# NNLightSwitcher_eMMC_SD.net
KiCad netlist of a schematic drawn in Altium Designer
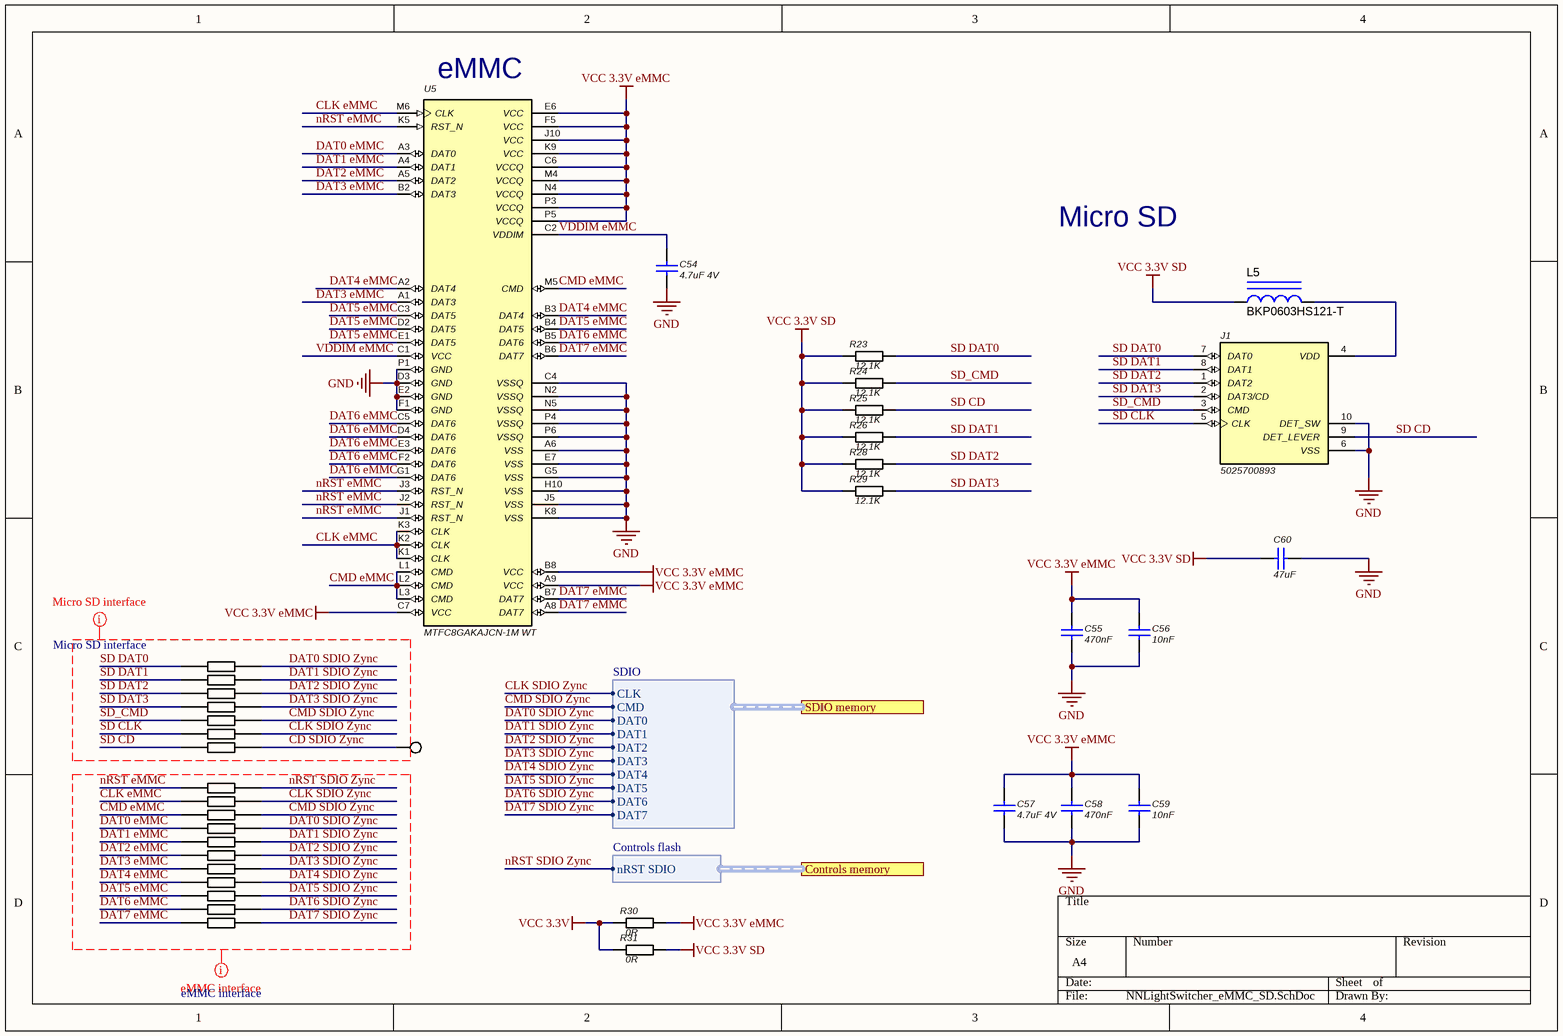
[diagram p0: NNLightSwitcher_eMMC_SD.SchDoc]

(export (version "E")
  (design (tool "Eeschema 10.0.6"))
  (components
    (comp (ref "C54")
      (value "4.7uF 4V")
      (footprint "0402")
      (libsource (lib "NNLightSwitcher") (part "Capacitor 4.7uF 4V"))
    )
    (comp (ref "C55")
      (value "470nF")
      (footprint "0402")
      (libsource (lib "NNLightSwitcher") (part "Capacitor 470nF"))
    )
    (comp (ref "C56")
      (value "10nF")
      (footprint "0402")
      (libsource (lib "NNLightSwitcher") (part "Capacitor 10nF"))
    )
    (comp (ref "C57")
      (value "4.7uF 4V")
      (footprint "0402")
      (libsource (lib "NNLightSwitcher") (part "Capacitor 4.7uF 4V"))
    )
    (comp (ref "C58")
      (value "470nF")
      (footprint "0402")
      (libsource (lib "NNLightSwitcher") (part "Capacitor 470nF"))
    )
    (comp (ref "C59")
      (value "10nF")
      (footprint "0402")
      (libsource (lib "NNLightSwitcher") (part "Capacitor 10nF"))
    )
    (comp (ref "C60")
      (value "47uF")
      (footprint "Res_0805")
      (libsource (lib "NNLightSwitcher") (part "Capacitor 47uF"))
    )
    (comp (ref "J1")
      (value "5025700893")
      (footprint "MOLEX_5025700893")
      (description "1.10mm Pitch microSD Memory Card Connector%2C Normal Mount Surface Mount%2C Push-Push Type")
      (libsource (lib "NNLightSwitcher") (part "Micro SD connector"))
    )
    (comp (ref "L5")
      (value "BKP0603HS121-T")
      (footprint "*0603")
      (description "Inductor, Multilayer, Ferrite bad")
      (fields (field (name "PARTNUMBER") "LQG15HS3N9S02D") (field (name "MANUFACTURER") "MuRata"))
      (libsource (lib "NNLightSwitcher") (part "BKP0603HS121-T"))
    )
    (comp (ref "R23")
      (value "12.1K")
      (footprint "0402")
      (libsource (lib "NNLightSwitcher") (part "Resistor 12.1K"))
    )
    (comp (ref "R24")
      (value "12.1K")
      (footprint "0402")
      (libsource (lib "NNLightSwitcher") (part "Resistor 12.1K"))
    )
    (comp (ref "R25")
      (value "12.1K")
      (footprint "0402")
      (libsource (lib "NNLightSwitcher") (part "Resistor 12.1K"))
    )
    (comp (ref "R26")
      (value "12.1K")
      (footprint "0402")
      (libsource (lib "NNLightSwitcher") (part "Resistor 12.1K"))
    )
    (comp (ref "R28")
      (value "12.1K")
      (footprint "0402")
      (libsource (lib "NNLightSwitcher") (part "Resistor 12.1K"))
    )
    (comp (ref "R29")
      (value "12.1K")
      (footprint "0402")
      (libsource (lib "NNLightSwitcher") (part "Resistor 12.1K"))
    )
    (comp (ref "R30")
      (value "0R")
      (footprint "0402")
      (libsource (lib "NNLightSwitcher") (part "Resistor 0R"))
    )
    (comp (ref "R31")
      (value "0R")
      (footprint "0402")
      (libsource (lib "NNLightSwitcher") (part "Resistor 0R"))
    )
    (comp (ref "RN25")
      (value "EXB-2HV431JV")
      (footprint "*RESCAXE50P380X160X55-16N")
      (description "Res Thick Film Array")
      (libsource (lib "NNLightSwitcher") (part "EXB-2HV431JV"))
    )
    (comp (ref "RN26")
      (value "EXB-2HV431JV")
      (footprint "*RESCAXE50P380X160X55-16N")
      (description "Res Thick Film Array")
      (libsource (lib "NNLightSwitcher") (part "EXB-2HV431JV"))
    )
    (comp (ref "RN27")
      (value "EXB-2HV431JV")
      (footprint "*RESCAXE50P380X160X55-16N")
      (description "Res Thick Film Array")
      (libsource (lib "NNLightSwitcher") (part "EXB-2HV431JV"))
    )
    (comp (ref "TP66")
      (value "Test point")
      (footprint "Testpoint_with_pad")
      (description "Test Point, Miniature, SMT")
      (libsource (lib "NNLightSwitcher") (part "Test point"))
    )
    (comp (ref "U5")
      (value "MTFC8GAKAJCN-1M WT")
      (footprint "*BGA153N50P14X14_1150X1300X100_MTFC4GACAAAM-1M_WT(Primary)")
      (description "J54A eMMC 32G ECCN: 3A991 / HTS: 8542.32.0070")
      (libsource (lib "NNLightSwitcher") (part "MTFC4GACAAAM-1M_WT"))
    )
  )
  (nets
    (net (code "4") (name "/CD SDIO Zync") (class "Default")
      (node (ref "RN25") (pin "15") (pinfunction "2_15") (pintype "passive"))
      (node (ref "TP66") (pin "1") (pintype "passive"))
    )
    (net (code "5") (name "/CLK SDIO Zync") (class "Default")
      (node (ref "RN25") (pin "11") (pinfunction "2_11") (pintype "passive"))
      (node (ref "RN26") (pin "14") (pinfunction "2_14") (pintype "passive"))
    )
    (net (code "6") (name "/CLK eMMC") (class "Default")
      (node (ref "RN26") (pin "3") (pinfunction "1_3") (pintype "passive"))
      (node (ref "U5") (pin "K1") (pinfunction "CLK_K1") (pintype "bidirectional"))
      (node (ref "U5") (pin "K2") (pinfunction "CLK_K2") (pintype "bidirectional"))
      (node (ref "U5") (pin "K3") (pinfunction "CLK_K3") (pintype "bidirectional"))
      (node (ref "U5") (pin "M6") (pinfunction "CLK_M6") (pintype "input"))
    )
    (net (code "7") (name "/CMD SDIO Zync") (class "Default")
      (node (ref "RN25") (pin "14") (pinfunction "2_14") (pintype "passive"))
      (node (ref "RN26") (pin "11") (pinfunction "2_11") (pintype "passive"))
    )
    (net (code "8") (name "/CMD eMMC") (class "Default")
      (node (ref "RN26") (pin "6") (pinfunction "1_6") (pintype "passive"))
      (node (ref "U5") (pin "L1") (pinfunction "CMD_L1") (pintype "bidirectional"))
      (node (ref "U5") (pin "L2") (pinfunction "CMD_L2") (pintype "bidirectional"))
      (node (ref "U5") (pin "L3") (pinfunction "CMD_L3") (pintype "bidirectional"))
      (node (ref "U5") (pin "M5") (pinfunction "CMD_M5") (pintype "bidirectional"))
    )
    (net (code "9") (name "/DAT0 SDIO Zync") (class "Default")
      (node (ref "RN25") (pin "9") (pinfunction "2_9") (pintype "passive"))
      (node (ref "RN26") (pin "16") (pinfunction "2_16") (pintype "passive"))
    )
    (net (code "10") (name "/DAT0 eMMC") (class "Default")
      (node (ref "RN26") (pin "1") (pinfunction "1_1") (pintype "passive"))
      (node (ref "U5") (pin "A3") (pinfunction "DAT0_A3") (pintype "bidirectional"))
    )
    (net (code "11") (name "/DAT1 SDIO Zync") (class "Default")
      (node (ref "RN25") (pin "10") (pinfunction "2_10") (pintype "passive"))
      (node (ref "RN26") (pin "15") (pinfunction "2_15") (pintype "passive"))
    )
    (net (code "12") (name "/DAT1 eMMC") (class "Default")
      (node (ref "RN26") (pin "2") (pinfunction "1_2") (pintype "passive"))
      (node (ref "U5") (pin "A4") (pinfunction "DAT1_A4") (pintype "bidirectional"))
    )
    (net (code "13") (name "/DAT2 SDIO Zync") (class "Default")
      (node (ref "RN25") (pin "12") (pinfunction "2_12") (pintype "passive"))
      (node (ref "RN26") (pin "13") (pinfunction "2_13") (pintype "passive"))
    )
    (net (code "14") (name "/DAT2 eMMC") (class "Default")
      (node (ref "RN26") (pin "4") (pinfunction "1_4") (pintype "passive"))
      (node (ref "U5") (pin "A5") (pinfunction "DAT2_A5") (pintype "bidirectional"))
    )
    (net (code "15") (name "/DAT3 SDIO Zync") (class "Default")
      (node (ref "RN25") (pin "13") (pinfunction "2_13") (pintype "passive"))
      (node (ref "RN26") (pin "12") (pinfunction "2_12") (pintype "passive"))
    )
    (net (code "16") (name "/DAT3 eMMC") (class "Default")
      (node (ref "RN26") (pin "5") (pinfunction "1_5") (pintype "passive"))
      (node (ref "U5") (pin "A1") (pinfunction "DAT3_A1") (pintype "bidirectional"))
      (node (ref "U5") (pin "B2") (pinfunction "DAT3_B2") (pintype "bidirectional"))
    )
    (net (code "17") (name "/DAT4 SDIO Zync") (class "Default")
      (node (ref "RN26") (pin "10") (pinfunction "2_10") (pintype "passive"))
    )
    (net (code "18") (name "/DAT4 eMMC") (class "Default")
      (node (ref "RN26") (pin "7") (pinfunction "1_7") (pintype "passive"))
      (node (ref "U5") (pin "A2") (pinfunction "DAT4_A2") (pintype "bidirectional"))
      (node (ref "U5") (pin "B3") (pinfunction "DAT4_B3") (pintype "bidirectional"))
    )
    (net (code "19") (name "/DAT5 SDIO Zync") (class "Default")
      (node (ref "RN26") (pin "9") (pinfunction "2_9") (pintype "passive"))
    )
    (net (code "20") (name "/DAT5 eMMC") (class "Default")
      (node (ref "RN26") (pin "8") (pinfunction "1_8") (pintype "passive"))
      (node (ref "U5") (pin "B4") (pinfunction "DAT5_B4") (pintype "bidirectional"))
      (node (ref "U5") (pin "C3") (pinfunction "DAT5_C3") (pintype "bidirectional"))
      (node (ref "U5") (pin "D2") (pinfunction "DAT5_D2") (pintype "bidirectional"))
      (node (ref "U5") (pin "E1") (pinfunction "DAT5_E1") (pintype "bidirectional"))
    )
    (net (code "21") (name "/DAT6 SDIO Zync") (class "Default")
      (node (ref "RN27") (pin "9") (pinfunction "2_9") (pintype "passive"))
    )
    (net (code "22") (name "/DAT6 eMMC") (class "Default")
      (node (ref "RN27") (pin "8") (pinfunction "1_8") (pintype "passive"))
      (node (ref "U5") (pin "B5") (pinfunction "DAT6_B5") (pintype "bidirectional"))
      (node (ref "U5") (pin "C5") (pinfunction "DAT6_C5") (pintype "bidirectional"))
      (node (ref "U5") (pin "D4") (pinfunction "DAT6_D4") (pintype "bidirectional"))
      (node (ref "U5") (pin "E3") (pinfunction "DAT6_E3") (pintype "bidirectional"))
      (node (ref "U5") (pin "F2") (pinfunction "DAT6_F2") (pintype "bidirectional"))
      (node (ref "U5") (pin "G1") (pinfunction "DAT6_G1") (pintype "bidirectional"))
    )
    (net (code "23") (name "/DAT7 SDIO Zync") (class "Default")
      (node (ref "RN27") (pin "10") (pinfunction "2_10") (pintype "passive"))
    )
    (net (code "24") (name "/DAT7 eMMC") (class "Default")
      (node (ref "RN27") (pin "7") (pinfunction "1_7") (pintype "passive"))
      (node (ref "U5") (pin "A8") (pinfunction "DAT7_A8") (pintype "bidirectional"))
      (node (ref "U5") (pin "B6") (pinfunction "DAT7_B6") (pintype "bidirectional"))
      (node (ref "U5") (pin "B7") (pinfunction "DAT7_B7") (pintype "bidirectional"))
    )
    (net (code "25") (name "/SD CD") (class "Default")
      (node (ref "J1") (pin "9") (pinfunction "DET_LEVER_9") (pintype "passive"))
      (node (ref "R25") (pin "2") (pinfunction "2_2") (pintype "passive"))
      (node (ref "RN25") (pin "2") (pinfunction "1_2") (pintype "passive"))
    )
    (net (code "26") (name "/SD CLK") (class "Default")
      (node (ref "J1") (pin "5") (pinfunction "CLK_5") (pintype "bidirectional"))
      (node (ref "RN25") (pin "6") (pinfunction "1_6") (pintype "passive"))
    )
    (net (code "27") (name "/SD DAT0") (class "Default")
      (node (ref "J1") (pin "7") (pinfunction "DAT0_7") (pintype "bidirectional"))
      (node (ref "R23") (pin "2") (pinfunction "2_2") (pintype "passive"))
      (node (ref "RN25") (pin "8") (pinfunction "1_8") (pintype "passive"))
    )
    (net (code "28") (name "/SD DAT1") (class "Default")
      (node (ref "J1") (pin "8") (pinfunction "DAT1_8") (pintype "bidirectional"))
      (node (ref "R26") (pin "2") (pinfunction "2_2") (pintype "passive"))
      (node (ref "RN25") (pin "7") (pinfunction "1_7") (pintype "passive"))
    )
    (net (code "29") (name "/SD DAT2") (class "Default")
      (node (ref "J1") (pin "1") (pinfunction "DAT2_1") (pintype "bidirectional"))
      (node (ref "R28") (pin "2") (pinfunction "2_2") (pintype "passive"))
      (node (ref "RN25") (pin "5") (pinfunction "1_5") (pintype "passive"))
    )
    (net (code "30") (name "/SD DAT3") (class "Default")
      (node (ref "J1") (pin "2") (pinfunction "DAT3/CD_2") (pintype "bidirectional"))
      (node (ref "R29") (pin "2") (pinfunction "2_2") (pintype "passive"))
      (node (ref "RN25") (pin "4") (pinfunction "1_4") (pintype "passive"))
    )
    (net (code "31") (name "/SD_CMD") (class "Default")
      (node (ref "J1") (pin "3") (pinfunction "CMD_3") (pintype "bidirectional"))
      (node (ref "R24") (pin "2") (pinfunction "2_2") (pintype "passive"))
      (node (ref "RN25") (pin "3") (pinfunction "1_3") (pintype "passive"))
    )
    (net (code "32") (name "/VDDIM eMMC") (class "Default")
      (node (ref "C54") (pin "1") (pinfunction "1_1") (pintype "passive"))
      (node (ref "U5") (pin "C1") (pinfunction "VCC_C1") (pintype "bidirectional"))
      (node (ref "U5") (pin "C2") (pinfunction "VDDIM_C2") (pintype "power_in"))
    )
    (net (code "33") (name "/nRST SDIO Zync") (class "Default")
      (node (ref "RN25") (pin "16") (pinfunction "2_16") (pintype "passive"))
    )
    (net (code "34") (name "/nRST eMMC") (class "Default")
      (node (ref "RN25") (pin "1") (pinfunction "1_1") (pintype "passive"))
      (node (ref "U5") (pin "J1") (pinfunction "RST_N_J1") (pintype "bidirectional"))
      (node (ref "U5") (pin "J2") (pinfunction "RST_N_J2") (pintype "bidirectional"))
      (node (ref "U5") (pin "J3") (pinfunction "RST_N_J3") (pintype "bidirectional"))
      (node (ref "U5") (pin "K5") (pinfunction "RST_N_K5") (pintype "input"))
    )
    (net (code "37") (name "GND") (class "Default")
      (node (ref "C54") (pin "2") (pinfunction "2_2") (pintype "passive"))
      (node (ref "C55") (pin "2") (pinfunction "2_2") (pintype "passive"))
      (node (ref "C56") (pin "2") (pinfunction "2_2") (pintype "passive"))
      (node (ref "C57") (pin "2") (pinfunction "2_2") (pintype "passive"))
      (node (ref "C58") (pin "2") (pinfunction "2_2") (pintype "passive"))
      (node (ref "C59") (pin "2") (pinfunction "2_2") (pintype "passive"))
      (node (ref "C60") (pin "1") (pinfunction "1_1") (pintype "passive"))
      (node (ref "J1") (pin "10") (pinfunction "DET_SW_10") (pintype "passive"))
      (node (ref "J1") (pin "6") (pinfunction "VSS_6") (pintype "power_in"))
      (node (ref "U5") (pin "A6") (pinfunction "VSS_A6") (pintype "power_in"))
      (node (ref "U5") (pin "C4") (pinfunction "VSSQ_C4") (pintype "power_in"))
      (node (ref "U5") (pin "D3") (pinfunction "GND_D3") (pintype "bidirectional"))
      (node (ref "U5") (pin "E2") (pinfunction "GND_E2") (pintype "bidirectional"))
      (node (ref "U5") (pin "E7") (pinfunction "VSS_E7") (pintype "power_in"))
      (node (ref "U5") (pin "F1") (pinfunction "GND_F1") (pintype "bidirectional"))
      (node (ref "U5") (pin "G5") (pinfunction "VSS_G5") (pintype "power_in"))
      (node (ref "U5") (pin "H10") (pinfunction "VSS_H10") (pintype "power_in"))
      (node (ref "U5") (pin "J5") (pinfunction "VSS_J5") (pintype "power_in"))
      (node (ref "U5") (pin "K8") (pinfunction "VSS_K8") (pintype "power_in"))
      (node (ref "U5") (pin "N2") (pinfunction "VSSQ_N2") (pintype "power_in"))
      (node (ref "U5") (pin "N5") (pinfunction "VSSQ_N5") (pintype "power_in"))
      (node (ref "U5") (pin "P1") (pinfunction "GND_P1") (pintype "bidirectional"))
      (node (ref "U5") (pin "P4") (pinfunction "VSSQ_P4") (pintype "power_in"))
      (node (ref "U5") (pin "P6") (pinfunction "VSSQ_P6") (pintype "power_in"))
    )
    (net (code "38") (name "Net-(J1-VDD)") (class "Default")
      (node (ref "J1") (pin "4") (pinfunction "VDD_4") (pintype "power_in"))
      (node (ref "L5") (pin "2") (pinfunction "2_2") (pintype "passive"))
    )
    (net (code "39") (name "VCC 3.3V") (class "Default")
      (node (ref "R30") (pin "1") (pinfunction "1_1") (pintype "passive"))
      (node (ref "R31") (pin "1") (pinfunction "1_1") (pintype "passive"))
    )
    (net (code "40") (name "VCC 3.3V SD") (class "Default")
      (node (ref "C60") (pin "2") (pinfunction "2_2") (pintype "passive"))
      (node (ref "L5") (pin "1") (pinfunction "1_1") (pintype "passive"))
      (node (ref "R23") (pin "1") (pinfunction "1_1") (pintype "passive"))
      (node (ref "R24") (pin "1") (pinfunction "1_1") (pintype "passive"))
      (node (ref "R25") (pin "1") (pinfunction "1_1") (pintype "passive"))
      (node (ref "R26") (pin "1") (pinfunction "1_1") (pintype "passive"))
      (node (ref "R28") (pin "1") (pinfunction "1_1") (pintype "passive"))
      (node (ref "R29") (pin "1") (pinfunction "1_1") (pintype "passive"))
      (node (ref "R31") (pin "2") (pinfunction "2_2") (pintype "passive"))
    )
    (net (code "41") (name "VCC 3.3V eMMC") (class "Default")
      (node (ref "C55") (pin "1") (pinfunction "1_1") (pintype "passive"))
      (node (ref "C56") (pin "1") (pinfunction "1_1") (pintype "passive"))
      (node (ref "C57") (pin "1") (pinfunction "1_1") (pintype "passive"))
      (node (ref "C58") (pin "1") (pinfunction "1_1") (pintype "passive"))
      (node (ref "C59") (pin "1") (pinfunction "1_1") (pintype "passive"))
      (node (ref "R30") (pin "2") (pinfunction "2_2") (pintype "passive"))
      (node (ref "U5") (pin "A9") (pinfunction "VCC_A9") (pintype "bidirectional"))
      (node (ref "U5") (pin "B8") (pinfunction "VCC_B8") (pintype "bidirectional"))
      (node (ref "U5") (pin "C6") (pinfunction "VCCQ_C6") (pintype "power_in"))
      (node (ref "U5") (pin "C7") (pinfunction "VCC_C7") (pintype "bidirectional"))
      (node (ref "U5") (pin "E6") (pinfunction "VCC_E6") (pintype "power_in"))
      (node (ref "U5") (pin "F5") (pinfunction "VCC_F5") (pintype "power_in"))
      (node (ref "U5") (pin "J10") (pinfunction "VCC_J10") (pintype "power_in"))
      (node (ref "U5") (pin "K9") (pinfunction "VCC_K9") (pintype "power_in"))
      (node (ref "U5") (pin "M4") (pinfunction "VCCQ_M4") (pintype "power_in"))
      (node (ref "U5") (pin "N4") (pinfunction "VCCQ_N4") (pintype "power_in"))
      (node (ref "U5") (pin "P3") (pinfunction "VCCQ_P3") (pintype "power_in"))
      (node (ref "U5") (pin "P5") (pinfunction "VCCQ_P5") (pintype "power_in"))
    )
  )
)
